# DMB-4770-8-IN-8-OUT.net
KiCad netlist of a schematic drawn in EAGLE
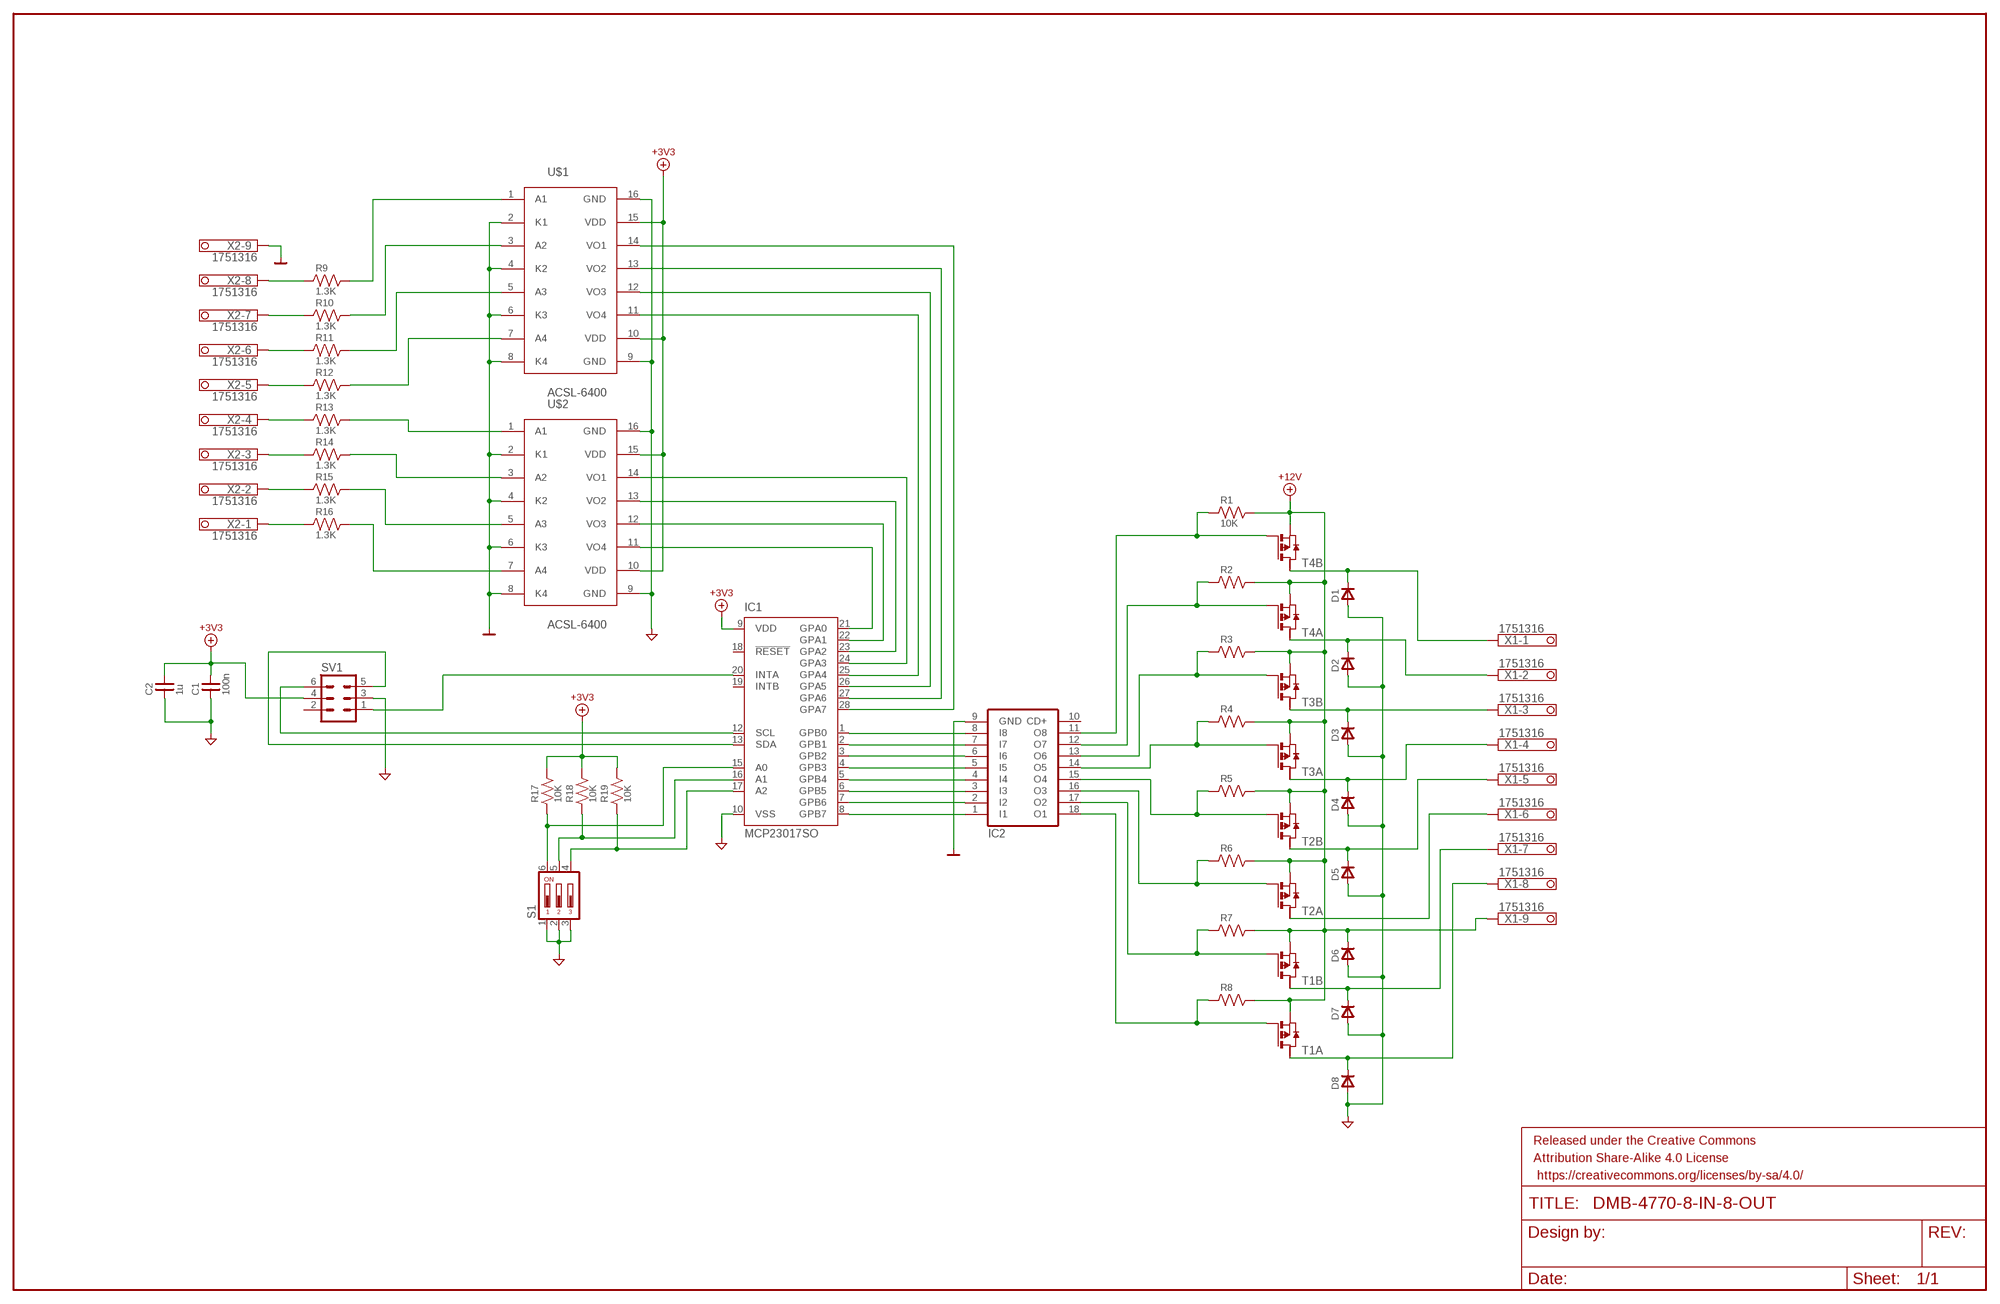
[diagram p0: schematic, sheet 1]

(export (version "E")
  (design (tool "Eeschema 10.0.6"))
  (components
    (comp (ref "C1")
      (value "100n")
      (footprint "eagle-import:C0805")
      (libsource (lib "eagle-import") (part "C0805"))
    )
    (comp (ref "C2")
      (value "1u")
      (footprint "eagle-import:C0805")
      (libsource (lib "eagle-import") (part "C0805"))
    )
    (comp (ref "D1")
      (value "DSMA")
      (footprint "eagle-import:DSMA")
      (libsource (lib "eagle-import") (part "DSMA"))
    )
    (comp (ref "D2")
      (value "DSMA")
      (footprint "eagle-import:DSMA")
      (libsource (lib "eagle-import") (part "DSMA"))
    )
    (comp (ref "D3")
      (value "DSMA")
      (footprint "eagle-import:DSMA")
      (libsource (lib "eagle-import") (part "DSMA"))
    )
    (comp (ref "D4")
      (value "DSMA")
      (footprint "eagle-import:DSMA")
      (libsource (lib "eagle-import") (part "DSMA"))
    )
    (comp (ref "D5")
      (value "DSMA")
      (footprint "eagle-import:DSMA")
      (libsource (lib "eagle-import") (part "DSMA"))
    )
    (comp (ref "D6")
      (value "DSMA")
      (footprint "eagle-import:DSMA")
      (libsource (lib "eagle-import") (part "DSMA"))
    )
    (comp (ref "D7")
      (value "DSMA")
      (footprint "eagle-import:DSMA")
      (libsource (lib "eagle-import") (part "DSMA"))
    )
    (comp (ref "D8")
      (value "DSMA")
      (footprint "eagle-import:DSMA")
      (libsource (lib "eagle-import") (part "DSMA"))
    )
    (comp (ref "FRAME1")
      (value "FRAME-LEDGER")
      (footprint "eagle-import:CREATIVE_COMMONS")
      (libsource (lib "eagle-import") (part "FRAME-LEDGER"))
    )
    (comp (ref "IC1")
      (value "MCP23017SO")
      (footprint "eagle-import:SO28W")
      (fields (field (name "MF") "MICROCHIP") (field (name "MPN") "MCP23017-E/SO"))
      (libsource (lib "eagle-import") (part "MCP23017SO"))
    )
    (comp (ref "IC2")
      (value "ULN2803A")
      (footprint "eagle-import:DIL18")
      (libsource (lib "eagle-import") (part "ULN2803A"))
    )
    (comp (ref "R1")
      (value "10K")
      (footprint "eagle-import:R0805")
      (libsource (lib "eagle-import") (part "RU0805"))
    )
    (comp (ref "R2")
      (value "RU0805")
      (footprint "eagle-import:R0805")
      (libsource (lib "eagle-import") (part "RU0805"))
    )
    (comp (ref "R3")
      (value "RU0805")
      (footprint "eagle-import:R0805")
      (libsource (lib "eagle-import") (part "RU0805"))
    )
    (comp (ref "R4")
      (value "RU0805")
      (footprint "eagle-import:R0805")
      (libsource (lib "eagle-import") (part "RU0805"))
    )
    (comp (ref "R5")
      (value "RU0805")
      (footprint "eagle-import:R0805")
      (libsource (lib "eagle-import") (part "RU0805"))
    )
    (comp (ref "R6")
      (value "RU0805")
      (footprint "eagle-import:R0805")
      (libsource (lib "eagle-import") (part "RU0805"))
    )
    (comp (ref "R7")
      (value "RU0805")
      (footprint "eagle-import:R0805")
      (libsource (lib "eagle-import") (part "RU0805"))
    )
    (comp (ref "R8")
      (value "RU0805")
      (footprint "eagle-import:R0805")
      (libsource (lib "eagle-import") (part "RU0805"))
    )
    (comp (ref "R9")
      (value "1.3K")
      (footprint "eagle-import:R0805")
      (libsource (lib "eagle-import") (part "RU0805"))
    )
    (comp (ref "R10")
      (value "1.3K")
      (footprint "eagle-import:R0805")
      (libsource (lib "eagle-import") (part "RU0805"))
    )
    (comp (ref "R11")
      (value "1.3K")
      (footprint "eagle-import:R0805")
      (libsource (lib "eagle-import") (part "RU0805"))
    )
    (comp (ref "R12")
      (value "1.3K")
      (footprint "eagle-import:R0805")
      (libsource (lib "eagle-import") (part "RU0805"))
    )
    (comp (ref "R13")
      (value "1.3K")
      (footprint "eagle-import:R0805")
      (libsource (lib "eagle-import") (part "RU0805"))
    )
    (comp (ref "R14")
      (value "1.3K")
      (footprint "eagle-import:R0805")
      (libsource (lib "eagle-import") (part "RU0805"))
    )
    (comp (ref "R15")
      (value "1.3K")
      (footprint "eagle-import:R0805")
      (libsource (lib "eagle-import") (part "RU0805"))
    )
    (comp (ref "R16")
      (value "1.3K")
      (footprint "eagle-import:R0805")
      (libsource (lib "eagle-import") (part "RU0805"))
    )
    (comp (ref "R17")
      (value "10K")
      (footprint "eagle-import:R0805")
      (libsource (lib "eagle-import") (part "RU0805"))
    )
    (comp (ref "R18")
      (value "10K")
      (footprint "eagle-import:R0805")
      (libsource (lib "eagle-import") (part "RU0805"))
    )
    (comp (ref "R19")
      (value "10K")
      (footprint "eagle-import:R0805")
      (libsource (lib "eagle-import") (part "RU0805"))
    )
    (comp (ref "S1")
      (value "DIP03YL")
      (footprint "eagle-import:DIP03YL")
      (libsource (lib "eagle-import") (part "DIP03YL"))
    )
    (comp (ref "SV1")
      (value "ML6")
      (footprint "eagle-import:ML6")
      (libsource (lib "eagle-import") (part "ML6"))
    )
    (comp (ref "T1")
      (value "PMOS2SO8")
      (footprint "eagle-import:SO8")
      (libsource (lib "eagle-import") (part "PMOS2SO8"))
    )
    (comp (ref "T2")
      (value "PMOS2SO8")
      (footprint "eagle-import:SO8")
      (libsource (lib "eagle-import") (part "PMOS2SO8"))
    )
    (comp (ref "T3")
      (value "PMOS2SO8")
      (footprint "eagle-import:SO8")
      (libsource (lib "eagle-import") (part "PMOS2SO8"))
    )
    (comp (ref "T4")
      (value "PMOS2SO8")
      (footprint "eagle-import:SO8")
      (libsource (lib "eagle-import") (part "PMOS2SO8"))
    )
    (comp (ref "U$1")
      (value "ACSL-6400")
      (footprint "eagle-import:SO16")
      (libsource (lib "eagle-import") (part "ACSL-6400"))
    )
    (comp (ref "U$2")
      (value "ACSL-6400")
      (footprint "eagle-import:SO16")
      (libsource (lib "eagle-import") (part "ACSL-6400"))
    )
    (comp (ref "X1")
      (value "1751316")
      (footprint "eagle-import:1751316")
      (libsource (lib "eagle-import") (part "1751316"))
    )
    (comp (ref "X2")
      (value "1751316")
      (footprint "eagle-import:1751316")
      (libsource (lib "eagle-import") (part "1751316"))
    )
  )
  (nets
    (net (code "1") (name "Net-(IC1-A0)") (class "Default")
      (node (ref "IC1") (pin "15") (pinfunction "A0_15") (pintype "input"))
      (node (ref "R17") (pin "1") (pinfunction "1_1") (pintype "passive"))
      (node (ref "S1") (pin "6") (pinfunction "6_6") (pintype "passive"))
    )
    (net (code "2") (name "Net-(IC1-A1)") (class "Default")
      (node (ref "IC1") (pin "16") (pinfunction "A1_16") (pintype "input"))
      (node (ref "R18") (pin "1") (pinfunction "1_1") (pintype "passive"))
      (node (ref "S1") (pin "5") (pinfunction "5_5") (pintype "passive"))
    )
    (net (code "3") (name "Net-(IC1-A2)") (class "Default")
      (node (ref "IC1") (pin "17") (pinfunction "A2_17") (pintype "input"))
      (node (ref "R19") (pin "1") (pinfunction "1_1") (pintype "passive"))
      (node (ref "S1") (pin "4") (pinfunction "4_4") (pintype "passive"))
    )
    (net (code "4") (name "Net-(IC1-GPA0)") (class "Default")
      (node (ref "IC1") (pin "21") (pinfunction "GPA0_21") (pintype "bidirectional"))
      (node (ref "U$2") (pin "11") (pinfunction "VO4_11") (pintype "bidirectional"))
    )
    (net (code "5") (name "Net-(IC1-GPA1)") (class "Default")
      (node (ref "IC1") (pin "22") (pinfunction "GPA1_22") (pintype "bidirectional"))
      (node (ref "U$2") (pin "12") (pinfunction "VO3_12") (pintype "bidirectional"))
    )
    (net (code "6") (name "Net-(IC1-GPA2)") (class "Default")
      (node (ref "IC1") (pin "23") (pinfunction "GPA2_23") (pintype "bidirectional"))
      (node (ref "U$2") (pin "13") (pinfunction "VO2_13") (pintype "bidirectional"))
    )
    (net (code "7") (name "Net-(IC1-GPA3)") (class "Default")
      (node (ref "IC1") (pin "24") (pinfunction "GPA3_24") (pintype "bidirectional"))
      (node (ref "U$2") (pin "14") (pinfunction "VO1_14") (pintype "bidirectional"))
    )
    (net (code "8") (name "Net-(IC1-GPA4)") (class "Default")
      (node (ref "IC1") (pin "25") (pinfunction "GPA4_25") (pintype "bidirectional"))
      (node (ref "U$1") (pin "11") (pinfunction "VO4_11") (pintype "bidirectional"))
    )
    (net (code "9") (name "Net-(IC1-GPA5)") (class "Default")
      (node (ref "IC1") (pin "26") (pinfunction "GPA5_26") (pintype "bidirectional"))
      (node (ref "U$1") (pin "12") (pinfunction "VO3_12") (pintype "bidirectional"))
    )
    (net (code "10") (name "Net-(IC1-GPA6)") (class "Default")
      (node (ref "IC1") (pin "27") (pinfunction "GPA6_27") (pintype "bidirectional"))
      (node (ref "U$1") (pin "13") (pinfunction "VO2_13") (pintype "bidirectional"))
    )
    (net (code "11") (name "Net-(IC1-GPA7)") (class "Default")
      (node (ref "IC1") (pin "28") (pinfunction "GPA7_28") (pintype "bidirectional"))
      (node (ref "U$1") (pin "14") (pinfunction "VO1_14") (pintype "bidirectional"))
    )
    (net (code "12") (name "Net-(IC1-GPB0)") (class "Default")
      (node (ref "IC1") (pin "1") (pinfunction "GPB0_1") (pintype "bidirectional"))
      (node (ref "IC2") (pin "8") (pinfunction "I8_8") (pintype "input"))
    )
    (net (code "13") (name "Net-(IC1-GPB1)") (class "Default")
      (node (ref "IC1") (pin "2") (pinfunction "GPB1_2") (pintype "bidirectional"))
      (node (ref "IC2") (pin "7") (pinfunction "I7_7") (pintype "input"))
    )
    (net (code "14") (name "Net-(IC1-GPB2)") (class "Default")
      (node (ref "IC1") (pin "3") (pinfunction "GPB2_3") (pintype "bidirectional"))
      (node (ref "IC2") (pin "6") (pinfunction "I6_6") (pintype "input"))
    )
    (net (code "15") (name "Net-(IC1-GPB3)") (class "Default")
      (node (ref "IC1") (pin "4") (pinfunction "GPB3_4") (pintype "bidirectional"))
      (node (ref "IC2") (pin "5") (pinfunction "I5_5") (pintype "input"))
    )
    (net (code "16") (name "Net-(IC1-GPB4)") (class "Default")
      (node (ref "IC1") (pin "5") (pinfunction "GPB4_5") (pintype "bidirectional"))
      (node (ref "IC2") (pin "4") (pinfunction "I4_4") (pintype "input"))
    )
    (net (code "17") (name "Net-(IC1-GPB5)") (class "Default")
      (node (ref "IC1") (pin "6") (pinfunction "GPB5_6") (pintype "bidirectional"))
      (node (ref "IC2") (pin "3") (pinfunction "I3_3") (pintype "input"))
    )
    (net (code "18") (name "Net-(IC1-GPB6)") (class "Default")
      (node (ref "IC1") (pin "7") (pinfunction "GPB6_7") (pintype "bidirectional"))
      (node (ref "IC2") (pin "2") (pinfunction "I2_2") (pintype "input"))
    )
    (net (code "19") (name "Net-(IC1-GPB7)") (class "Default")
      (node (ref "IC1") (pin "8") (pinfunction "GPB7_8") (pintype "bidirectional"))
      (node (ref "IC2") (pin "1") (pinfunction "I1_1") (pintype "input"))
    )
    (net (code "20") (name "Net-(IC1-INTA)") (class "Default")
      (node (ref "IC1") (pin "20") (pinfunction "INTA_20") (pintype "output"))
      (node (ref "SV1") (pin "1") (pinfunction "1_1") (pintype "passive"))
    )
    (net (code "21") (name "Net-(IC1-SCL)") (class "Default")
      (node (ref "IC1") (pin "12") (pinfunction "SCL_12") (pintype "input"))
      (node (ref "SV1") (pin "6") (pinfunction "6_6") (pintype "passive"))
    )
    (net (code "22") (name "Net-(IC1-SDA)") (class "Default")
      (node (ref "IC1") (pin "13") (pinfunction "SDA_13") (pintype "bidirectional"))
      (node (ref "SV1") (pin "5") (pinfunction "5_5") (pintype "passive"))
    )
    (net (code "23") (name "Net-(IC2-O1)") (class "Default")
      (node (ref "IC2") (pin "18") (pinfunction "O1_18") (pintype "open_collector"))
      (node (ref "R8") (pin "1") (pinfunction "1_1") (pintype "passive"))
      (node (ref "T1") (pin "2") (pinfunction "G_2") (pintype "passive"))
    )
    (net (code "24") (name "Net-(IC2-O2)") (class "Default")
      (node (ref "IC2") (pin "17") (pinfunction "O2_17") (pintype "open_collector"))
      (node (ref "R7") (pin "1") (pinfunction "1_1") (pintype "passive"))
      (node (ref "T1") (pin "4") (pinfunction "G_4") (pintype "passive"))
    )
    (net (code "25") (name "Net-(IC2-O3)") (class "Default")
      (node (ref "IC2") (pin "16") (pinfunction "O3_16") (pintype "open_collector"))
      (node (ref "R6") (pin "1") (pinfunction "1_1") (pintype "passive"))
      (node (ref "T2") (pin "2") (pinfunction "G_2") (pintype "passive"))
    )
    (net (code "26") (name "Net-(IC2-O4)") (class "Default")
      (node (ref "IC2") (pin "15") (pinfunction "O4_15") (pintype "open_collector"))
      (node (ref "R5") (pin "1") (pinfunction "1_1") (pintype "passive"))
      (node (ref "T2") (pin "4") (pinfunction "G_4") (pintype "passive"))
    )
    (net (code "27") (name "Net-(IC2-O5)") (class "Default")
      (node (ref "IC2") (pin "14") (pinfunction "O5_14") (pintype "open_collector"))
      (node (ref "R4") (pin "1") (pinfunction "1_1") (pintype "passive"))
      (node (ref "T3") (pin "2") (pinfunction "G_2") (pintype "passive"))
    )
    (net (code "28") (name "Net-(IC2-O6)") (class "Default")
      (node (ref "IC2") (pin "13") (pinfunction "O6_13") (pintype "open_collector"))
      (node (ref "R3") (pin "1") (pinfunction "1_1") (pintype "passive"))
      (node (ref "T3") (pin "4") (pinfunction "G_4") (pintype "passive"))
    )
    (net (code "29") (name "Net-(IC2-O7)") (class "Default")
      (node (ref "IC2") (pin "12") (pinfunction "O7_12") (pintype "open_collector"))
      (node (ref "R2") (pin "1") (pinfunction "1_1") (pintype "passive"))
      (node (ref "T4") (pin "2") (pinfunction "G_2") (pintype "passive"))
    )
    (net (code "30") (name "Net-(IC2-O8)") (class "Default")
      (node (ref "IC2") (pin "11") (pinfunction "O8_11") (pintype "open_collector"))
      (node (ref "R1") (pin "1") (pinfunction "1_1") (pintype "passive"))
      (node (ref "T4") (pin "4") (pinfunction "G_4") (pintype "passive"))
    )
    (net (code "31") (name "Net-(T1A-D)") (class "Default")
      (node (ref "D8") (pin "C") (pinfunction "C_C") (pintype "passive"))
      (node (ref "T1") (pin "7") (pinfunction "D_7") (pintype "passive"))
      (node (ref "X1") (pin "8") (pinfunction "K_8") (pintype "passive"))
    )
    (net (code "32") (name "Net-(T1B-D)") (class "Default")
      (node (ref "D7") (pin "C") (pinfunction "C_C") (pintype "passive"))
      (node (ref "T1") (pin "6") (pinfunction "D_6") (pintype "passive"))
      (node (ref "X1") (pin "7") (pinfunction "K_7") (pintype "passive"))
    )
    (net (code "33") (name "Net-(T2A-D)") (class "Default")
      (node (ref "T2") (pin "7") (pinfunction "D_7") (pintype "passive"))
      (node (ref "X1") (pin "6") (pinfunction "K_6") (pintype "passive"))
    )
    (net (code "34") (name "Net-(T2B-D)") (class "Default")
      (node (ref "D5") (pin "C") (pinfunction "C_C") (pintype "passive"))
      (node (ref "T2") (pin "6") (pinfunction "D_6") (pintype "passive"))
      (node (ref "X1") (pin "5") (pinfunction "K_5") (pintype "passive"))
    )
    (net (code "35") (name "Net-(T3A-D)") (class "Default")
      (node (ref "D4") (pin "C") (pinfunction "C_C") (pintype "passive"))
      (node (ref "T3") (pin "7") (pinfunction "D_7") (pintype "passive"))
      (node (ref "X1") (pin "4") (pinfunction "K_4") (pintype "passive"))
    )
    (net (code "36") (name "Net-(T3B-D)") (class "Default")
      (node (ref "D3") (pin "C") (pinfunction "C_C") (pintype "passive"))
      (node (ref "T3") (pin "6") (pinfunction "D_6") (pintype "passive"))
      (node (ref "X1") (pin "3") (pinfunction "K_3") (pintype "passive"))
    )
    (net (code "37") (name "Net-(T4A-D)") (class "Default")
      (node (ref "D2") (pin "C") (pinfunction "C_C") (pintype "passive"))
      (node (ref "T4") (pin "7") (pinfunction "D_7") (pintype "passive"))
      (node (ref "X1") (pin "2") (pinfunction "K_2") (pintype "passive"))
    )
    (net (code "38") (name "Net-(T4B-D)") (class "Default")
      (node (ref "D1") (pin "C") (pinfunction "C_C") (pintype "passive"))
      (node (ref "T4") (pin "6") (pinfunction "D_6") (pintype "passive"))
      (node (ref "X1") (pin "1") (pinfunction "K_1") (pintype "passive"))
    )
    (net (code "39") (name "Net-(U$1-A1)") (class "Default")
      (node (ref "R9") (pin "2") (pinfunction "2_2") (pintype "passive"))
      (node (ref "U$1") (pin "1") (pinfunction "A1_1") (pintype "input"))
    )
    (net (code "40") (name "Net-(U$1-A2)") (class "Default")
      (node (ref "R10") (pin "2") (pinfunction "2_2") (pintype "passive"))
      (node (ref "U$1") (pin "3") (pinfunction "A2_3") (pintype "input"))
    )
    (net (code "41") (name "Net-(U$1-A3)") (class "Default")
      (node (ref "R11") (pin "2") (pinfunction "2_2") (pintype "passive"))
      (node (ref "U$1") (pin "5") (pinfunction "A3_5") (pintype "input"))
    )
    (net (code "42") (name "Net-(U$1-A4)") (class "Default")
      (node (ref "R12") (pin "2") (pinfunction "2_2") (pintype "passive"))
      (node (ref "U$1") (pin "7") (pinfunction "A4_7") (pintype "input"))
    )
    (net (code "43") (name "Net-(U$2-A1)") (class "Default")
      (node (ref "R13") (pin "2") (pinfunction "2_2") (pintype "passive"))
      (node (ref "U$2") (pin "1") (pinfunction "A1_1") (pintype "input"))
    )
    (net (code "44") (name "Net-(U$2-A2)") (class "Default")
      (node (ref "R14") (pin "2") (pinfunction "2_2") (pintype "passive"))
      (node (ref "U$2") (pin "3") (pinfunction "A2_3") (pintype "input"))
    )
    (net (code "45") (name "Net-(U$2-A3)") (class "Default")
      (node (ref "R15") (pin "2") (pinfunction "2_2") (pintype "passive"))
      (node (ref "U$2") (pin "5") (pinfunction "A3_5") (pintype "input"))
    )
    (net (code "46") (name "Net-(U$2-A4)") (class "Default")
      (node (ref "R16") (pin "2") (pinfunction "2_2") (pintype "passive"))
      (node (ref "U$2") (pin "7") (pinfunction "A4_7") (pintype "input"))
    )
    (net (code "47") (name "Net-(X2A-K)") (class "Default")
      (node (ref "R16") (pin "1") (pinfunction "1_1") (pintype "passive"))
      (node (ref "X2") (pin "1") (pinfunction "K_1") (pintype "passive"))
    )
    (net (code "48") (name "Net-(X2B-K)") (class "Default")
      (node (ref "R15") (pin "1") (pinfunction "1_1") (pintype "passive"))
      (node (ref "X2") (pin "2") (pinfunction "K_2") (pintype "passive"))
    )
    (net (code "49") (name "Net-(X2C-K)") (class "Default")
      (node (ref "R14") (pin "1") (pinfunction "1_1") (pintype "passive"))
      (node (ref "X2") (pin "3") (pinfunction "K_3") (pintype "passive"))
    )
    (net (code "50") (name "Net-(X2D-K)") (class "Default")
      (node (ref "R13") (pin "1") (pinfunction "1_1") (pintype "passive"))
      (node (ref "X2") (pin "4") (pinfunction "K_4") (pintype "passive"))
    )
    (net (code "51") (name "Net-(X2E-K)") (class "Default")
      (node (ref "R12") (pin "1") (pinfunction "1_1") (pintype "passive"))
      (node (ref "X2") (pin "5") (pinfunction "K_5") (pintype "passive"))
    )
    (net (code "52") (name "Net-(X2F-K)") (class "Default")
      (node (ref "R11") (pin "1") (pinfunction "1_1") (pintype "passive"))
      (node (ref "X2") (pin "6") (pinfunction "K_6") (pintype "passive"))
    )
    (net (code "53") (name "Net-(X2G-K)") (class "Default")
      (node (ref "R10") (pin "1") (pinfunction "1_1") (pintype "passive"))
      (node (ref "X2") (pin "7") (pinfunction "K_7") (pintype "passive"))
    )
    (net (code "54") (name "Net-(X2H-K)") (class "Default")
      (node (ref "R9") (pin "1") (pinfunction "1_1") (pintype "passive"))
      (node (ref "X2") (pin "8") (pinfunction "K_8") (pintype "passive"))
    )
    (net (code "55") (name "V+3V3") (class "Default")
      (node (ref "C1") (pin "2") (pinfunction "2_2") (pintype "passive"))
      (node (ref "C2") (pin "2") (pinfunction "2_2") (pintype "passive"))
      (node (ref "IC1") (pin "9") (pinfunction "VDD_9") (pintype "power_in"))
      (node (ref "R17") (pin "2") (pinfunction "2_2") (pintype "passive"))
      (node (ref "R18") (pin "2") (pinfunction "2_2") (pintype "passive"))
      (node (ref "R19") (pin "2") (pinfunction "2_2") (pintype "passive"))
      (node (ref "SV1") (pin "4") (pinfunction "4_4") (pintype "passive"))
      (node (ref "U$1") (pin "10") (pinfunction "VDD_10") (pintype "power_in"))
      (node (ref "U$1") (pin "15") (pinfunction "VDD_15") (pintype "power_in"))
      (node (ref "U$2") (pin "10") (pinfunction "VDD_10") (pintype "power_in"))
      (node (ref "U$2") (pin "15") (pinfunction "VDD_15") (pintype "power_in"))
    )
    (net (code "56") (name "V+12-24VV") (class "Default")
      (node (ref "D6") (pin "C") (pinfunction "C_C") (pintype "passive"))
      (node (ref "R1") (pin "2") (pinfunction "2_2") (pintype "passive"))
      (node (ref "R2") (pin "2") (pinfunction "2_2") (pintype "passive"))
      (node (ref "R3") (pin "2") (pinfunction "2_2") (pintype "passive"))
      (node (ref "R4") (pin "2") (pinfunction "2_2") (pintype "passive"))
      (node (ref "R5") (pin "2") (pinfunction "2_2") (pintype "passive"))
      (node (ref "R6") (pin "2") (pinfunction "2_2") (pintype "passive"))
      (node (ref "R7") (pin "2") (pinfunction "2_2") (pintype "passive"))
      (node (ref "R8") (pin "2") (pinfunction "2_2") (pintype "passive"))
      (node (ref "T1") (pin "1") (pinfunction "S_1") (pintype "passive"))
      (node (ref "T1") (pin "3") (pinfunction "S_3") (pintype "passive"))
      (node (ref "T2") (pin "1") (pinfunction "S_1") (pintype "passive"))
      (node (ref "T2") (pin "3") (pinfunction "S_3") (pintype "passive"))
      (node (ref "T3") (pin "1") (pinfunction "S_1") (pintype "passive"))
      (node (ref "T3") (pin "3") (pinfunction "S_3") (pintype "passive"))
      (node (ref "T4") (pin "1") (pinfunction "S_1") (pintype "passive"))
      (node (ref "T4") (pin "3") (pinfunction "S_3") (pintype "passive"))
      (node (ref "X1") (pin "9") (pinfunction "K_9") (pintype "passive"))
    )
    (net (code "57") (name "VDG") (class "Default")
      (node (ref "C1") (pin "1") (pinfunction "1_1") (pintype "passive"))
      (node (ref "C2") (pin "1") (pinfunction "1_1") (pintype "passive"))
      (node (ref "D1") (pin "A") (pinfunction "A_A") (pintype "passive"))
      (node (ref "D2") (pin "A") (pinfunction "A_A") (pintype "passive"))
      (node (ref "D3") (pin "A") (pinfunction "A_A") (pintype "passive"))
      (node (ref "D4") (pin "A") (pinfunction "A_A") (pintype "passive"))
      (node (ref "D5") (pin "A") (pinfunction "A_A") (pintype "passive"))
      (node (ref "D6") (pin "A") (pinfunction "A_A") (pintype "passive"))
      (node (ref "D7") (pin "A") (pinfunction "A_A") (pintype "passive"))
      (node (ref "D8") (pin "A") (pinfunction "A_A") (pintype "passive"))
      (node (ref "IC1") (pin "10") (pinfunction "VSS_10") (pintype "power_in"))
      (node (ref "S1") (pin "1") (pinfunction "1_1") (pintype "passive"))
      (node (ref "S1") (pin "2") (pinfunction "2_2") (pintype "passive"))
      (node (ref "S1") (pin "3") (pinfunction "3_3") (pintype "passive"))
      (node (ref "SV1") (pin "3") (pinfunction "3_3") (pintype "passive"))
      (node (ref "U$1") (pin "16") (pinfunction "GND_16") (pintype "power_in"))
      (node (ref "U$1") (pin "9") (pinfunction "GND_9") (pintype "power_in"))
      (node (ref "U$2") (pin "16") (pinfunction "GND_16") (pintype "power_in"))
      (node (ref "U$2") (pin "9") (pinfunction "GND_9") (pintype "power_in"))
    )
    (net (code "58") (name "VG") (class "Default")
      (node (ref "IC2") (pin "9") (pinfunction "GND_9") (pintype "power_in"))
      (node (ref "U$1") (pin "2") (pinfunction "K1_2") (pintype "input"))
      (node (ref "U$1") (pin "4") (pinfunction "K2_4") (pintype "input"))
      (node (ref "U$1") (pin "6") (pinfunction "K3_6") (pintype "input"))
      (node (ref "U$1") (pin "8") (pinfunction "K4_8") (pintype "input"))
      (node (ref "U$2") (pin "2") (pinfunction "K1_2") (pintype "input"))
      (node (ref "U$2") (pin "4") (pinfunction "K2_4") (pintype "input"))
      (node (ref "U$2") (pin "6") (pinfunction "K3_6") (pintype "input"))
      (node (ref "U$2") (pin "8") (pinfunction "K4_8") (pintype "input"))
      (node (ref "X2") (pin "9") (pinfunction "K_9") (pintype "passive"))
    )
    (net (code "59") (name "unconnected-(IC1-INTB-Pad19)") (class "Default")
      (node (ref "IC1") (pin "19") (pinfunction "INTB_19") (pintype "output"))
    )
    (net (code "60") (name "unconnected-(IC1-~{RESET}-Pad18)") (class "Default")
      (node (ref "IC1") (pin "18") (pinfunction "~{RESET}_18") (pintype "input"))
    )
    (net (code "61") (name "unconnected-(IC2-CD+-Pad10)") (class "Default")
      (node (ref "IC2") (pin "10") (pinfunction "CD+_10") (pintype "passive"))
    )
    (net (code "62") (name "unconnected-(SV1-Pad2)") (class "Default")
      (node (ref "SV1") (pin "2") (pinfunction "2_2") (pintype "passive"))
    )
    (net (code "63") (name "unconnected-(T1A-D2-Pad8)") (class "Default")
      (node (ref "T1") (pin "8") (pinfunction "D2_8") (pintype "passive"))
    )
    (net (code "64") (name "unconnected-(T1B-D2-Pad5)") (class "Default")
      (node (ref "T1") (pin "5") (pinfunction "D2_5") (pintype "passive"))
    )
    (net (code "65") (name "unconnected-(T2A-D2-Pad8)") (class "Default")
      (node (ref "T2") (pin "8") (pinfunction "D2_8") (pintype "passive"))
    )
    (net (code "66") (name "unconnected-(T2B-D2-Pad5)") (class "Default")
      (node (ref "T2") (pin "5") (pinfunction "D2_5") (pintype "passive"))
    )
    (net (code "67") (name "unconnected-(T3A-D2-Pad8)") (class "Default")
      (node (ref "T3") (pin "8") (pinfunction "D2_8") (pintype "passive"))
    )
    (net (code "68") (name "unconnected-(T3B-D2-Pad5)") (class "Default")
      (node (ref "T3") (pin "5") (pinfunction "D2_5") (pintype "passive"))
    )
    (net (code "69") (name "unconnected-(T4A-D2-Pad8)") (class "Default")
      (node (ref "T4") (pin "8") (pinfunction "D2_8") (pintype "passive"))
    )
    (net (code "70") (name "unconnected-(T4B-D2-Pad5)") (class "Default")
      (node (ref "T4") (pin "5") (pinfunction "D2_5") (pintype "passive"))
    )
  )
)
